# Ethernet.net
KiCad netlist of a schematic drawn in Altium Designer
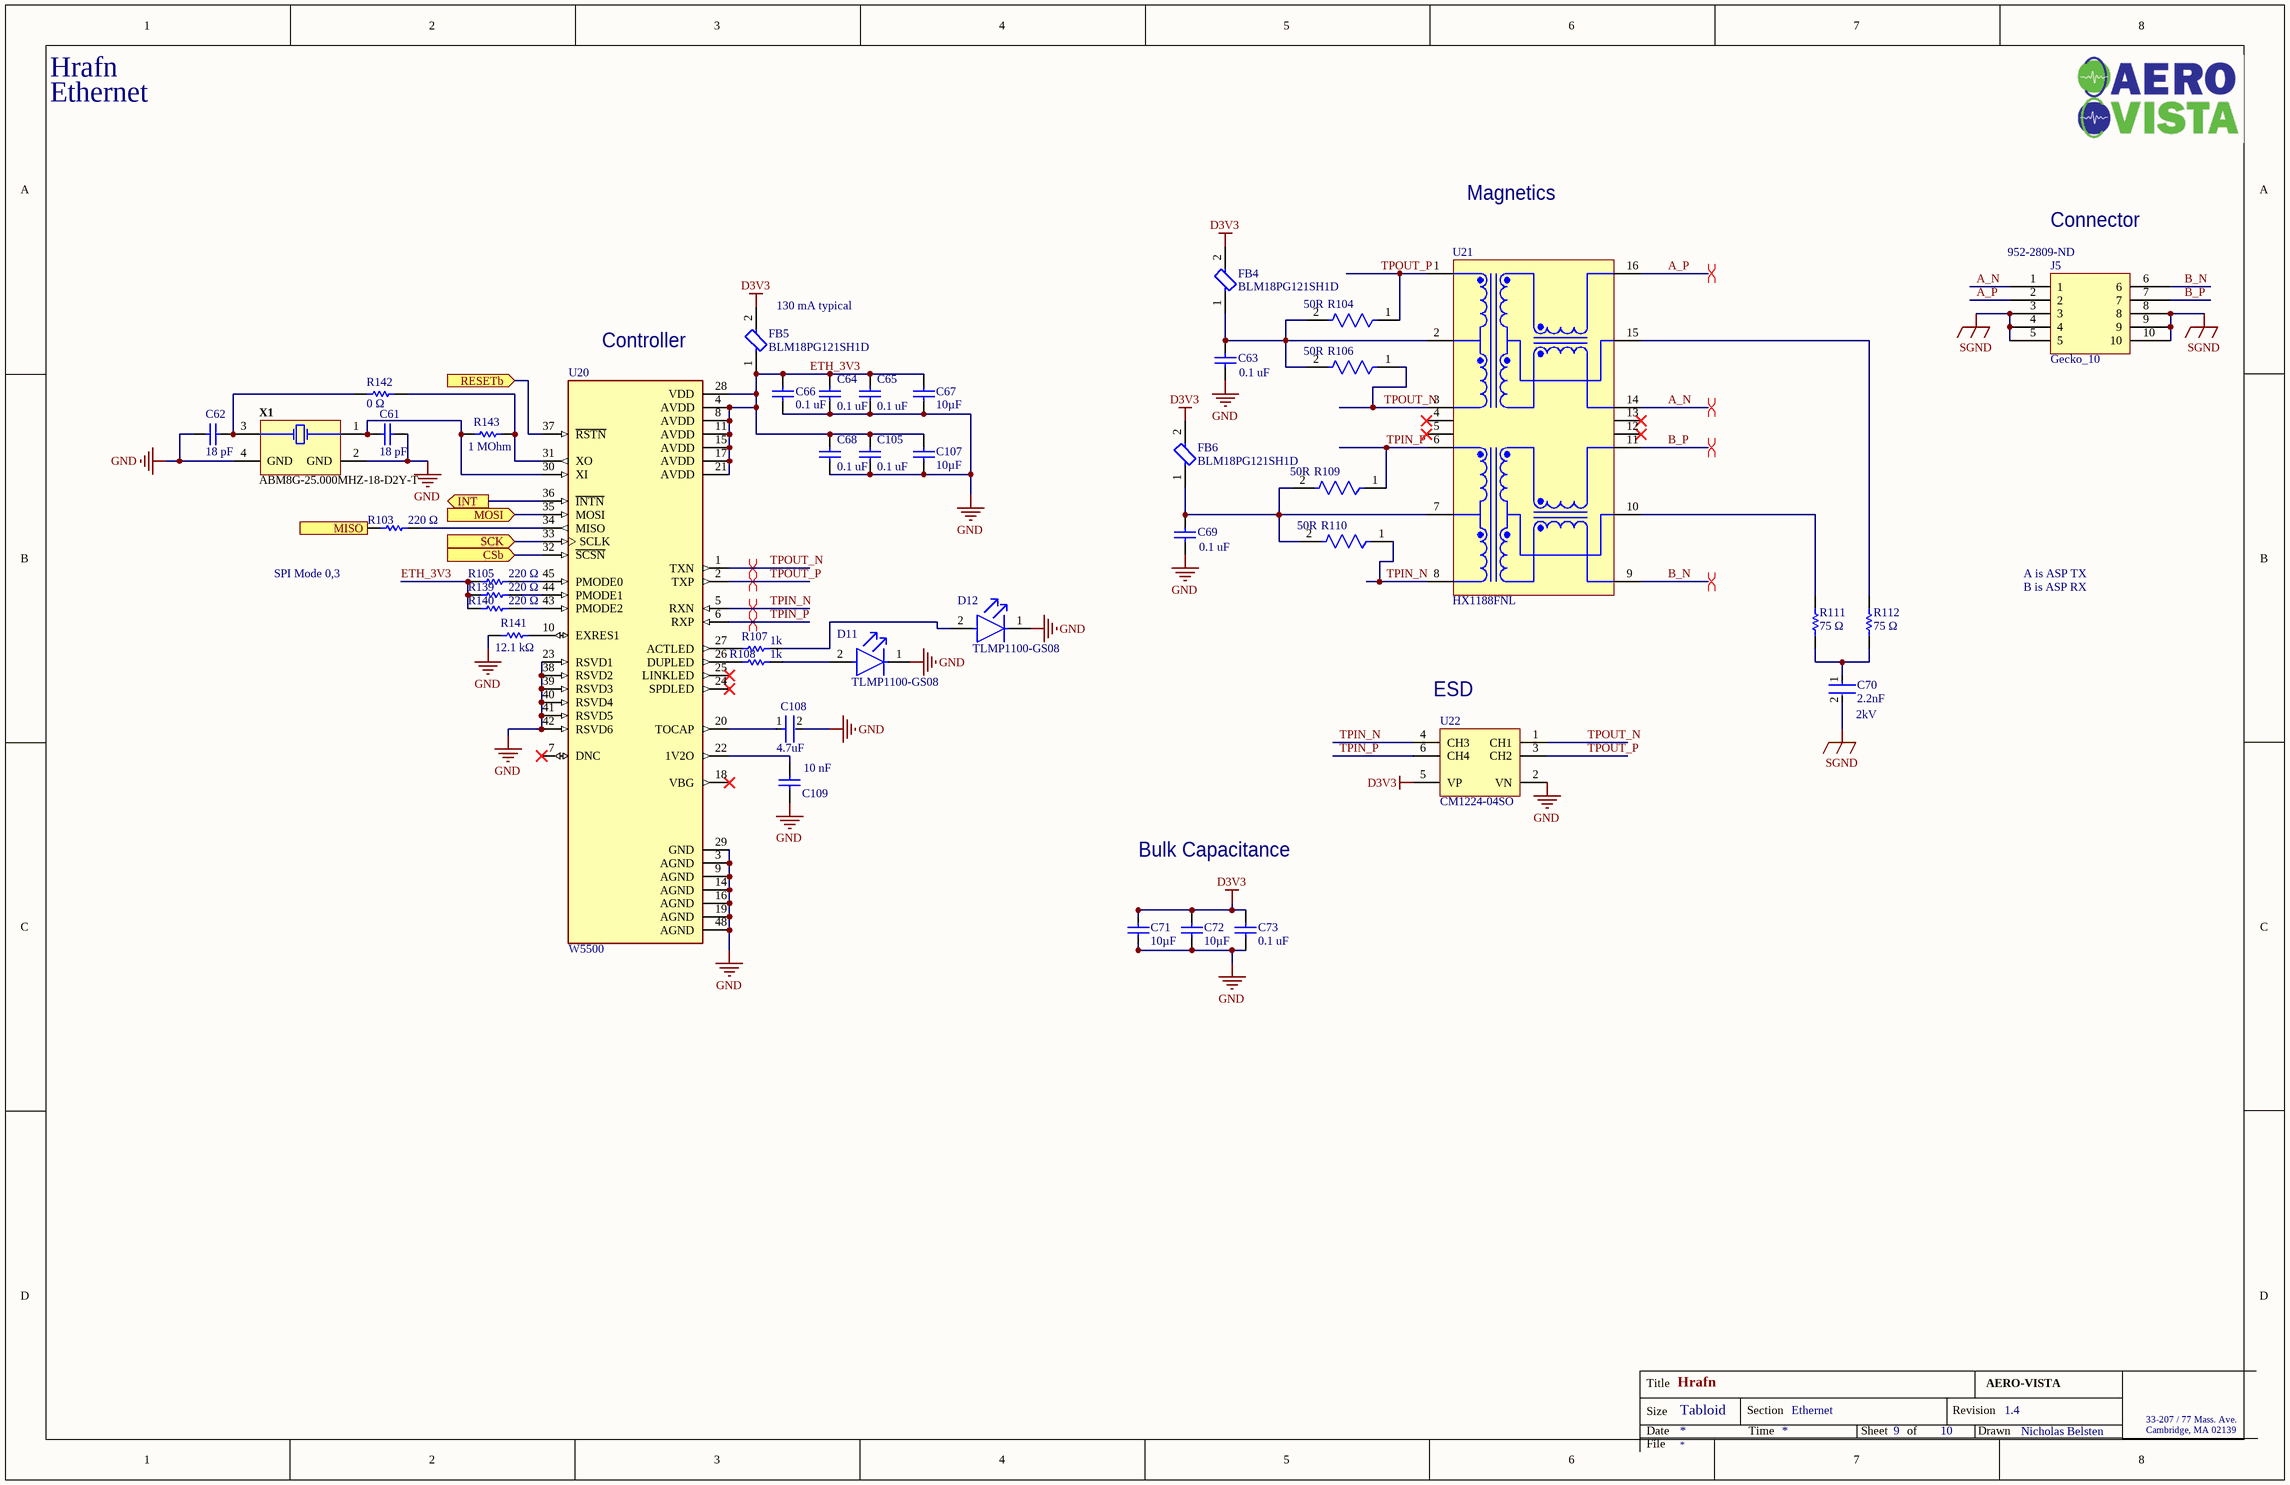
[diagram p0: Ethernet.SchDoc]

(export (version "E")
  (design (tool "Eeschema 10.0.6"))
  (components
    (comp (ref "C61")
      (value "GRM1555C1H180JA01D")
      (footprint "CAPC1005X55X25LL05T10")
      (fields (field (name "MANUFACTURER") "Murata") (field (name "CAPACITANCE") "18 pF"))
      (libsource (lib "Altium Content Vault") (part "CAP"))
    )
    (comp (ref "C62")
      (value "GRM1555C1H180JA01D")
      (footprint "CAPC1005X55X25LL05T10")
      (fields (field (name "MANUFACTURER") "Murata") (field (name "CAPACITANCE") "18 pF"))
      (libsource (lib "Altium Content Vault") (part "CAP"))
    )
    (comp (ref "C63")
      (value "0.1 uF")
      (footprint "CAPC0402(1005)60_L")
      (description "CAP 100nF 16V ±5% 0402 (1005 Metric) Thickness 0.6mm SMD")
      (fields (field (name "TOLERANCE") "Â±5%"))
      (libsource (lib "Altium Content Vault") (part "CAP"))
    )
    (comp (ref "C64")
      (value "0.1 uF")
      (footprint "CAPC0402(1005)60_L")
      (description "CAP 100nF 16V ±5% 0402 (1005 Metric) Thickness 0.6mm SMD")
      (fields (field (name "TOLERANCE") "Â±5%"))
      (libsource (lib "Altium Content Vault") (part "CAP"))
    )
    (comp (ref "C65")
      (value "0.1 uF")
      (footprint "CAPC0402(1005)60_L")
      (description "CAP 100nF 16V ±5% 0402 (1005 Metric) Thickness 0.6mm SMD")
      (fields (field (name "TOLERANCE") "Â±5%"))
      (libsource (lib "Altium Content Vault") (part "CAP"))
    )
    (comp (ref "C66")
      (value "0.1 uF")
      (footprint "CAPC0402(1005)60_L")
      (description "CAP 100nF 16V ±5% 0402 (1005 Metric) Thickness 0.6mm SMD")
      (fields (field (name "TOLERANCE") "Â±5%"))
      (libsource (lib "Altium Content Vault") (part "CAP"))
    )
    (comp (ref "C67")
      (value "EMK107BBJ106MA-T")
      (footprint "CAPC1608X100X35LL20T25")
      (description "Chip Capacitor, 10 uF, +/- 20%, 16 V, -55 to 85 degC, 0603 (1608 Metric), RoHS, Tape and Reel")
      (fields
        (field (name "CAPACITANCE") "10µF")
        (field (name "MANUFACTURER") "Taiyo Yuden")
        (field (name "TOLERANCE") "±20%")
      )
      (libsource (lib "Altium Content Vault") (part "CAP-NP-2"))
    )
    (comp (ref "C68")
      (value "0.1 uF")
      (footprint "CAPC0402(1005)60_L")
      (description "CAP 100nF 16V ±5% 0402 (1005 Metric) Thickness 0.6mm SMD")
      (fields (field (name "TOLERANCE") "Â±5%"))
      (libsource (lib "Altium Content Vault") (part "CAP"))
    )
    (comp (ref "C69")
      (value "0.1 uF")
      (footprint "CAPC0402(1005)60_L")
      (description "CAP 100nF 16V ±5% 0402 (1005 Metric) Thickness 0.6mm SMD")
      (fields (field (name "TOLERANCE") "Â±5%"))
      (libsource (lib "Altium Content Vault") (part "CAP"))
    )
    (comp (ref "C70")
      (value "2.2nF")
      (footprint "FP-CGA6P-MFG")
      (description "Cap Ceramic 2.2nF 2000V X7S 20% Pad SMD 1210 +125°C Automotive T/R")
      (fields (field (name "VOLTAGE RATING (DC)") "2kV") (field (name "TOLERANCE") "20%"))
      (libsource (lib "Altium Content Vault") (part "b4654b650e69147ec39a6b967a45e02"))
    )
    (comp (ref "C71")
      (value "EMK107BBJ106MA-T")
      (footprint "CAPC1608X100X35LL20T25")
      (description "Chip Capacitor, 10 uF, +/- 20%, 16 V, -55 to 85 degC, 0603 (1608 Metric), RoHS, Tape and Reel")
      (fields
        (field (name "CAPACITANCE") "10µF")
        (field (name "MANUFACTURER") "Taiyo Yuden")
        (field (name "TOLERANCE") "±20%")
      )
      (libsource (lib "Altium Content Vault") (part "CAP-NP-2"))
    )
    (comp (ref "C72")
      (value "EMK107BBJ106MA-T")
      (footprint "CAPC1608X100X35LL20T25")
      (description "Chip Capacitor, 10 uF, +/- 20%, 16 V, -55 to 85 degC, 0603 (1608 Metric), RoHS, Tape and Reel")
      (fields
        (field (name "CAPACITANCE") "10µF")
        (field (name "MANUFACTURER") "Taiyo Yuden")
        (field (name "TOLERANCE") "±20%")
      )
      (libsource (lib "Altium Content Vault") (part "CAP-NP-2"))
    )
    (comp (ref "C73")
      (value "0.1 uF")
      (footprint "CAPC0402(1005)60_L")
      (description "CAP 100nF 16V ±5% 0402 (1005 Metric) Thickness 0.6mm SMD")
      (fields (field (name "TOLERANCE") "Â±5%"))
      (libsource (lib "Altium Content Vault") (part "CAP"))
    )
    (comp (ref "C105")
      (value "0.1 uF")
      (footprint "CAPC0402(1005)60_L")
      (description "CAP 100nF 16V ±5% 0402 (1005 Metric) Thickness 0.6mm SMD")
      (fields (field (name "TOLERANCE") "Â±5%"))
      (libsource (lib "Altium Content Vault") (part "CAP"))
    )
    (comp (ref "C107")
      (value "EMK107BBJ106MA-T")
      (footprint "CAPC1608X100X35LL20T25")
      (description "Chip Capacitor, 10 uF, +/- 20%, 16 V, -55 to 85 degC, 0603 (1608 Metric), RoHS, Tape and Reel")
      (fields
        (field (name "CAPACITANCE") "10µF")
        (field (name "MANUFACTURER") "Taiyo Yuden")
        (field (name "TOLERANCE") "±20%")
      )
      (libsource (lib "Altium Content Vault") (part "CAP-NP-2"))
    )
    (comp (ref "C108")
      (value "GRM188R6YA475KE15D")
      (footprint "FP-GRM188-0_2-IPC_C")
      (description "Chip Multilayer Ceramic Capacitors for General Purpose, 0603, 4.7uF, X5R, 15%, 10%, 35V")
      (fields
        (field (name "CAPACITANCE") "4.7uF")
        (field (name "VOLTAGE") "35V")
        (field (name "TOLERANCE") "10%")
      )
      (libsource (lib "Altium Content Vault") (part "11868f565c42a9108669ba33697ecf6"))
    )
    (comp (ref "C109")
      (value "GRM155R71E103KA01D")
      (footprint "CAPC1005X55X25LL05T10")
      (fields (field (name "MANUFACTURER") "Murata") (field (name "CAPACITANCE") "10 nF"))
      (libsource (lib "Altium Content Vault") (part "CAP"))
    )
    (comp (ref "D11")
      (value "TLMP1100-GS08")
      (footprint "FP-6_541-5056_01-4-MFG")
      (description "LED GREEN 0603 SMD")
      (fields
        (field (name "MANUFACTURER") "Vishay")
        (field (name "OCTOPART") "https://octopart.com/tlmp1100-gs08-vishay-55433993")
      )
      (libsource (lib "Altium Content Vault") (part "8706943c75ba83719d021d2fdc84c58"))
    )
    (comp (ref "D12")
      (value "TLMP1100-GS08")
      (footprint "FP-6_541-5056_01-4-MFG")
      (description "LED GREEN 0603 SMD")
      (fields
        (field (name "MANUFACTURER") "Vishay")
        (field (name "OCTOPART") "https://octopart.com/tlmp1100-gs08-vishay-55433993")
      )
      (libsource (lib "Altium Content Vault") (part "8706943c75ba83719d021d2fdc84c58"))
    )
    (comp (ref "FB4")
      (value "BLM18PG121SH1D")
      (footprint "FP-BLM18-0_15-t0_8-IPC_C")
      (description "Chip Ferrite Bead, 0603, 120Ω @ 100MHz, 0.05Ω, 25%, 2A")
      (fields (field (name "TOLERANCE") "25%"))
      (libsource (lib "Altium Content Vault") (part "5f30dd21d616792df468990f7003faa"))
    )
    (comp (ref "FB5")
      (value "BLM18PG121SH1D")
      (footprint "FP-BLM18-0_15-t0_8-IPC_C")
      (description "Chip Ferrite Bead, 0603, 120Ω @ 100MHz, 0.05Ω, 25%, 2A")
      (fields (field (name "TOLERANCE") "25%"))
      (libsource (lib "Altium Content Vault") (part "5f30dd21d616792df468990f7003faa"))
    )
    (comp (ref "FB6")
      (value "BLM18PG121SH1D")
      (footprint "FP-BLM18-0_15-t0_8-IPC_C")
      (description "Chip Ferrite Bead, 0603, 120Ω @ 100MHz, 0.05Ω, 25%, 2A")
      (fields (field (name "TOLERANCE") "25%"))
      (libsource (lib "Altium Content Vault") (part "5f30dd21d616792df468990f7003faa"))
    )
    (comp (ref "J5")
      (value "Gecko_10")
      (footprint "GECK10-dup")
      (description "Headers & Wire Housings 1.25MM M VERT 3.0MM 2x5 POS")
      (fields (field (name "SUPPLIER PART NUMBER 1") "952-2809-ND"))
      (libsource (lib "Hrafn") (part "Gecko_10"))
    )
    (comp (ref "R103")
      (value "220 Ω")
      (footprint "RESC1005X40X25LL05T05")
      (fields (field (name "PART NUMBER") "CRCW040220K0FKED") (field (name "MANUFACTURER") "Vishay Dale"))
      (libsource (lib "Altium Content Vault") (part "RES"))
    )
    (comp (ref "R104")
      (value "CRCW060350R0FKEA")
      (footprint "FP-CRCW0603-e3-MFG")
      (description "RES Thick Film, 50Ω, 1%, 0.1W, 100ppm/°C, 0603")
      (fields (field (name "RESISTANCE") "50R") (field (name "TOLERANCE") "1%"))
      (libsource (lib "Altium Content Vault") (part "1029c3af85768c4190bb7ad29bc67b5"))
    )
    (comp (ref "R105")
      (value "220 Ω")
      (footprint "RESC1005X40X25LL05T05")
      (fields (field (name "PART NUMBER") "CRCW040220K0FKED") (field (name "MANUFACTURER") "Vishay Dale"))
      (libsource (lib "Altium Content Vault") (part "RES"))
    )
    (comp (ref "R106")
      (value "CRCW060350R0FKEA")
      (footprint "FP-CRCW0603-e3-MFG")
      (description "RES Thick Film, 50Ω, 1%, 0.1W, 100ppm/°C, 0603")
      (fields (field (name "RESISTANCE") "50R") (field (name "TOLERANCE") "1%"))
      (libsource (lib "Altium Content Vault") (part "1029c3af85768c4190bb7ad29bc67b5"))
    )
    (comp (ref "R107")
      (value "ERJ-2GEJ102X")
      (footprint "RESC1005X40X25LL05T05")
      (fields (field (name "MANUFACTURER") "Panasonic") (field (name "RESISTANCE") "1k"))
      (libsource (lib "Altium Content Vault") (part "RES"))
    )
    (comp (ref "R108")
      (value "ERJ-2GEJ102X")
      (footprint "RESC1005X40X25LL05T05")
      (fields (field (name "MANUFACTURER") "Panasonic") (field (name "RESISTANCE") "1k"))
      (libsource (lib "Altium Content Vault") (part "RES"))
    )
    (comp (ref "R109")
      (value "CRCW060350R0FKEA")
      (footprint "FP-CRCW0603-e3-MFG")
      (description "RES Thick Film, 50Ω, 1%, 0.1W, 100ppm/°C, 0603")
      (fields (field (name "RESISTANCE") "50R") (field (name "TOLERANCE") "1%"))
      (libsource (lib "Altium Content Vault") (part "1029c3af85768c4190bb7ad29bc67b5"))
    )
    (comp (ref "R110")
      (value "CRCW060350R0FKEA")
      (footprint "FP-CRCW0603-e3-MFG")
      (description "RES Thick Film, 50Ω, 1%, 0.1W, 100ppm/°C, 0603")
      (fields (field (name "RESISTANCE") "50R") (field (name "TOLERANCE") "1%"))
      (libsource (lib "Altium Content Vault") (part "1029c3af85768c4190bb7ad29bc67b5"))
    )
    (comp (ref "R111")
      (value "75 Ω")
      (footprint "RESC1005X40X25NL05T05")
      (fields (field (name "MANUFACTURER") "Panasonic") (field (name "PART NUMBER") "ERJ-2RKF75R0X"))
      (libsource (lib "Altium Content Vault") (part "RES"))
    )
    (comp (ref "R112")
      (value "75 Ω")
      (footprint "RESC1005X40X25NL05T05")
      (fields (field (name "MANUFACTURER") "Panasonic") (field (name "PART NUMBER") "ERJ-2RKF75R0X"))
      (libsource (lib "Altium Content Vault") (part "RES"))
    )
    (comp (ref "R139")
      (value "220 Ω")
      (footprint "RESC1005X40X25LL05T05")
      (fields (field (name "PART NUMBER") "CRCW040220K0FKED") (field (name "MANUFACTURER") "Vishay Dale"))
      (libsource (lib "Altium Content Vault") (part "RES"))
    )
    (comp (ref "R140")
      (value "220 Ω")
      (footprint "RESC1005X40X25LL05T05")
      (fields (field (name "PART NUMBER") "CRCW040220K0FKED") (field (name "MANUFACTURER") "Vishay Dale"))
      (libsource (lib "Altium Content Vault") (part "RES"))
    )
    (comp (ref "R141")
      (value "ERJ-2RKF1212X")
      (footprint "RESC1005X40X25LL05T05")
      (fields (field (name "MANUFACTURER") "Panasonic") (field (name "RESISTANCE") "12.1 kΩ"))
      (libsource (lib "Altium Content Vault") (part "RES"))
    )
    (comp (ref "R142")
      (value "ERJ2GE0R00X")
      (footprint "RESC1005X40X25LL05T05")
      (description "Chip Resistor, 0 Ohm, 0.1 W, -55 to 155 degC, 0402 (1005 Metric), RoHS, Tape and Reel")
      (fields
        (field (name "MANUFACTURER") "Panasonic")
        (field (name "RESISTANCE") "0 Ω")
        (field (name "TOLERANCE") "5%")
      )
      (libsource (lib "Altium Content Vault") (part "RES-2"))
    )
    (comp (ref "R143")
      (value "AC0402FR-071ML")
      (footprint "RESC1005X37X25LL05T10")
      (fields (field (name "MANUFACTURER") "Yageo") (field (name "RESISTANCE") "1 MOhm"))
      (libsource (lib "Altium Content Vault") (part "RES"))
    )
    (comp (ref "U20")
      (value "W5500")
      (footprint "TSQFP50P900X900X160-48L")
      (description "Socket Contact Silver 17-20 AWG Crimp Power")
      (fields (field (name "MF") "WIZnet"))
      (libsource (lib "W5500") (part "W5500"))
    )
    (comp (ref "U21")
      (value "HX1188FNL")
      (footprint "PULS-HX1188FNL-SMT-16_V")
      (description "Telecom Transformer 1:1/1:1, -40 to 85 degC, 16-Pin SMT, RoHS, Tube")
      (fields (field (name "MANUFACTURER") "Pulse Electronics"))
      (libsource (lib "Altium Content Vault") (part "PULS-HX1188FNL-16"))
    )
    (comp (ref "U22")
      (value "CM1224-04SO")
      (footprint "ONSC-SOT23-6-527AJ_V")
      (description "4-Channel Low Capacitance ESD Protection Array, 6-Pin SOT-23, Pb-Free, Tape and Reel")
      (fields (field (name "MANUFACTURER") "On Semiconductor"))
      (libsource (lib "Altium Content Vault") (part "ONSC-CM1224-SOT-23-6-527AJ"))
    )
    (comp (ref "X1")
      (value "ABM8G-25.000MHZ-18-D2Y-T")
      (footprint "ABRA-ABM8G_V")
      (fields (field (name "MANUFACTURER") "ABRACON") (field (name "TOLERANCE") "20PPM"))
      (libsource (lib "Altium Content Vault") (part "XTAL-1-3-4"))
    )
  )
  (nets
    (net (code "1") (name "/A_N") (class "Default")
      (node (ref "J5") (pin "1") (pinfunction "1_1") (pintype "passive"))
      (node (ref "U21") (pin "14") (pinfunction "TX-_14") (pintype "passive"))
    )
    (net (code "2") (name "/A_P") (class "Default")
      (node (ref "J5") (pin "2") (pinfunction "2_2") (pintype "passive"))
      (node (ref "U21") (pin "16") (pinfunction "TX+_16") (pintype "passive"))
    )
    (net (code "3") (name "/B_N") (class "Default")
      (node (ref "J5") (pin "6") (pinfunction "6_6") (pintype "passive"))
      (node (ref "U21") (pin "9") (pinfunction "RX-_9") (pintype "passive"))
    )
    (net (code "4") (name "/B_P") (class "Default")
      (node (ref "J5") (pin "7") (pinfunction "7_7") (pintype "passive"))
      (node (ref "U21") (pin "11") (pinfunction "RX+_11") (pintype "passive"))
    )
    (net (code "5") (name "/CSb") (class "Default")
      (node (ref "U20") (pin "32") (pinfunction "~{SCSN}_32") (pintype "input"))
    )
    (net (code "6") (name "/ETH_3V3") (class "Default")
      (node (ref "C105") (pin "2") (pinfunction "2_2") (pintype "passive"))
      (node (ref "C107") (pin "1") (pinfunction "1_1") (pintype "passive"))
      (node (ref "C64") (pin "2") (pinfunction "2_2") (pintype "passive"))
      (node (ref "C65") (pin "2") (pinfunction "2_2") (pintype "passive"))
      (node (ref "C66") (pin "1") (pinfunction "1_1") (pintype "passive"))
      (node (ref "C67") (pin "1") (pinfunction "1_1") (pintype "passive"))
      (node (ref "C68") (pin "2") (pinfunction "2_2") (pintype "passive"))
      (node (ref "FB5") (pin "1") (pinfunction "1_1") (pintype "passive"))
      (node (ref "R105") (pin "1") (pinfunction "1_1") (pintype "passive"))
      (node (ref "R139") (pin "1") (pinfunction "1_1") (pintype "passive"))
      (node (ref "R140") (pin "1") (pinfunction "1_1") (pintype "passive"))
      (node (ref "U20") (pin "11") (pinfunction "AVDD_11") (pintype "power_in"))
      (node (ref "U20") (pin "15") (pinfunction "AVDD_15") (pintype "power_in"))
      (node (ref "U20") (pin "17") (pinfunction "AVDD_17") (pintype "power_in"))
      (node (ref "U20") (pin "21") (pinfunction "AVDD_21") (pintype "power_in"))
      (node (ref "U20") (pin "28") (pinfunction "VDD_28") (pintype "power_in"))
      (node (ref "U20") (pin "4") (pinfunction "AVDD_4") (pintype "power_in"))
      (node (ref "U20") (pin "8") (pinfunction "AVDD_8") (pintype "power_in"))
    )
    (net (code "7") (name "/INT") (class "Default")
      (node (ref "U20") (pin "36") (pinfunction "~{INTN}_36") (pintype "input"))
    )
    (net (code "8") (name "/MISO") (class "Default")
      (node (ref "R103") (pin "1") (pinfunction "1_1") (pintype "passive"))
    )
    (net (code "9") (name "/MOSI") (class "Default")
      (node (ref "U20") (pin "35") (pinfunction "MOSI_35") (pintype "input"))
    )
    (net (code "10") (name "/RESETb") (class "Default")
      (node (ref "U20") (pin "37") (pinfunction "~{RSTN}_37") (pintype "input"))
    )
    (net (code "11") (name "/SCK") (class "Default")
      (node (ref "U20") (pin "33") (pinfunction "SCLK_33") (pintype "input"))
    )
    (net (code "12") (name "/TPIN_N") (class "Default")
      (node (ref "R110") (pin "1") (pinfunction "1_1") (pintype "passive"))
      (node (ref "U20") (pin "5") (pinfunction "RXN_5") (pintype "input"))
      (node (ref "U21") (pin "8") (pinfunction "RD-_8") (pintype "passive"))
      (node (ref "U22") (pin "4") (pinfunction "CH3_4") (pintype "passive"))
    )
    (net (code "13") (name "/TPIN_P") (class "Default")
      (node (ref "R109") (pin "1") (pinfunction "1_1") (pintype "passive"))
      (node (ref "U20") (pin "6") (pinfunction "RXP_6") (pintype "input"))
      (node (ref "U21") (pin "6") (pinfunction "RD+_6") (pintype "passive"))
      (node (ref "U22") (pin "6") (pinfunction "CH4_6") (pintype "passive"))
    )
    (net (code "14") (name "/TPOUT_N") (class "Default")
      (node (ref "R106") (pin "1") (pinfunction "1_1") (pintype "passive"))
      (node (ref "U20") (pin "1") (pinfunction "TXN_1") (pintype "output"))
      (node (ref "U21") (pin "3") (pinfunction "TD-_3") (pintype "passive"))
      (node (ref "U22") (pin "1") (pinfunction "CH1_1") (pintype "passive"))
    )
    (net (code "15") (name "/TPOUT_P") (class "Default")
      (node (ref "R104") (pin "1") (pinfunction "1_1") (pintype "passive"))
      (node (ref "U20") (pin "2") (pinfunction "TXP_2") (pintype "output"))
      (node (ref "U21") (pin "1") (pinfunction "TD+_1") (pintype "passive"))
      (node (ref "U22") (pin "3") (pinfunction "CH2_3") (pintype "passive"))
    )
    (net (code "16") (name "D3V3") (class "Default")
      (node (ref "C71") (pin "2") (pinfunction "2_2") (pintype "passive"))
      (node (ref "C72") (pin "2") (pinfunction "2_2") (pintype "passive"))
      (node (ref "C73") (pin "2") (pinfunction "2_2") (pintype "passive"))
      (node (ref "FB4") (pin "2") (pinfunction "2_2") (pintype "passive"))
      (node (ref "FB5") (pin "2") (pinfunction "2_2") (pintype "passive"))
      (node (ref "FB6") (pin "2") (pinfunction "2_2") (pintype "passive"))
      (node (ref "U22") (pin "5") (pinfunction "VP_5") (pintype "power_in"))
    )
    (net (code "17") (name "GND") (class "Default")
      (node (ref "C105") (pin "1") (pinfunction "1_1") (pintype "passive"))
      (node (ref "C107") (pin "2") (pinfunction "2_2") (pintype "passive"))
      (node (ref "C108") (pin "2") (pinfunction "2_2") (pintype "passive"))
      (node (ref "C109") (pin "1") (pinfunction "1_1") (pintype "passive"))
      (node (ref "C61") (pin "1") (pinfunction "1_1") (pintype "passive"))
      (node (ref "C62") (pin "2") (pinfunction "2_2") (pintype "passive"))
      (node (ref "C63") (pin "1") (pinfunction "1_1") (pintype "passive"))
      (node (ref "C64") (pin "1") (pinfunction "1_1") (pintype "passive"))
      (node (ref "C65") (pin "1") (pinfunction "1_1") (pintype "passive"))
      (node (ref "C66") (pin "2") (pinfunction "2_2") (pintype "passive"))
      (node (ref "C67") (pin "2") (pinfunction "2_2") (pintype "passive"))
      (node (ref "C68") (pin "1") (pinfunction "1_1") (pintype "passive"))
      (node (ref "C69") (pin "1") (pinfunction "1_1") (pintype "passive"))
      (node (ref "C71") (pin "1") (pinfunction "1_1") (pintype "passive"))
      (node (ref "C72") (pin "1") (pinfunction "1_1") (pintype "passive"))
      (node (ref "C73") (pin "1") (pinfunction "1_1") (pintype "passive"))
      (node (ref "D11") (pin "1") (pinfunction "C_1") (pintype "passive"))
      (node (ref "D12") (pin "1") (pinfunction "C_1") (pintype "passive"))
      (node (ref "R141") (pin "1") (pinfunction "1_1") (pintype "passive"))
      (node (ref "U20") (pin "14") (pinfunction "AGND_14") (pintype "power_in"))
      (node (ref "U20") (pin "16") (pinfunction "AGND_16") (pintype "power_in"))
      (node (ref "U20") (pin "19") (pinfunction "AGND_19") (pintype "power_in"))
      (node (ref "U20") (pin "23") (pinfunction "RSVD1_23") (pintype "input"))
      (node (ref "U20") (pin "29") (pinfunction "GND_29") (pintype "passive"))
      (node (ref "U20") (pin "3") (pinfunction "AGND_3") (pintype "power_in"))
      (node (ref "U20") (pin "38") (pinfunction "RSVD2_38") (pintype "input"))
      (node (ref "U20") (pin "39") (pinfunction "RSVD3_39") (pintype "input"))
      (node (ref "U20") (pin "40") (pinfunction "RSVD4_40") (pintype "input"))
      (node (ref "U20") (pin "41") (pinfunction "RSVD5_41") (pintype "input"))
      (node (ref "U20") (pin "42") (pinfunction "RSVD6_42") (pintype "input"))
      (node (ref "U20") (pin "48") (pinfunction "AGND_48") (pintype "power_in"))
      (node (ref "U20") (pin "9") (pinfunction "AGND_9") (pintype "power_in"))
      (node (ref "U22") (pin "2") (pinfunction "VN_2") (pintype "power_in"))
      (node (ref "X1") (pin "2") (pinfunction "GND_2") (pintype "power_in"))
      (node (ref "X1") (pin "4") (pinfunction "GND_4") (pintype "power_in"))
    )
    (net (code "18") (name "Net-(C70-Pad1)") (class "Default")
      (node (ref "C70") (pin "1") (pinfunction "1_1") (pintype "passive"))
      (node (ref "R111") (pin "1") (pinfunction "1_1") (pintype "passive"))
      (node (ref "R112") (pin "1") (pinfunction "1_1") (pintype "passive"))
    )
    (net (code "19") (name "Net-(D11-A)") (class "Default")
      (node (ref "D11") (pin "2") (pinfunction "A_2") (pintype "passive"))
      (node (ref "R108") (pin "2") (pinfunction "2_2") (pintype "passive"))
    )
    (net (code "20") (name "Net-(D12-A)") (class "Default")
      (node (ref "D12") (pin "2") (pinfunction "A_2") (pintype "passive"))
      (node (ref "R107") (pin "2") (pinfunction "2_2") (pintype "passive"))
    )
    (net (code "21") (name "Net-(R111-Pad2)") (class "Default")
      (node (ref "R111") (pin "2") (pinfunction "2_2") (pintype "passive"))
      (node (ref "U21") (pin "10") (pinfunction "CMT_10") (pintype "passive"))
    )
    (net (code "22") (name "Net-(R112-Pad2)") (class "Default")
      (node (ref "R112") (pin "2") (pinfunction "2_2") (pintype "passive"))
      (node (ref "U21") (pin "15") (pinfunction "CMT_15") (pintype "passive"))
    )
    (net (code "23") (name "Net-(U20-1V2O)") (class "Default")
      (node (ref "C109") (pin "2") (pinfunction "2_2") (pintype "passive"))
      (node (ref "U20") (pin "22") (pinfunction "1V2O_22") (pintype "output"))
    )
    (net (code "24") (name "Net-(U20-ACTLED)") (class "Default")
      (node (ref "R107") (pin "1") (pinfunction "1_1") (pintype "passive"))
      (node (ref "U20") (pin "27") (pinfunction "ACTLED_27") (pintype "output"))
    )
    (net (code "25") (name "Net-(U20-DUPLED)") (class "Default")
      (node (ref "R108") (pin "1") (pinfunction "1_1") (pintype "passive"))
      (node (ref "U20") (pin "26") (pinfunction "DUPLED_26") (pintype "output"))
    )
    (net (code "26") (name "Net-(U20-EXRES1)") (class "Default")
      (node (ref "R141") (pin "2") (pinfunction "2_2") (pintype "passive"))
      (node (ref "U20") (pin "10") (pinfunction "EXRES1_10") (pintype "bidirectional"))
    )
    (net (code "27") (name "Net-(U20-MISO)") (class "Default")
      (node (ref "R103") (pin "2") (pinfunction "2_2") (pintype "passive"))
      (node (ref "U20") (pin "34") (pinfunction "MISO_34") (pintype "output"))
    )
    (net (code "28") (name "Net-(U20-PMODE0)") (class "Default")
      (node (ref "R105") (pin "2") (pinfunction "2_2") (pintype "passive"))
      (node (ref "U20") (pin "45") (pinfunction "PMODE0_45") (pintype "input"))
    )
    (net (code "29") (name "Net-(U20-PMODE1)") (class "Default")
      (node (ref "R139") (pin "2") (pinfunction "2_2") (pintype "passive"))
      (node (ref "U20") (pin "44") (pinfunction "PMODE1_44") (pintype "input"))
    )
    (net (code "30") (name "Net-(U20-PMODE2)") (class "Default")
      (node (ref "R140") (pin "2") (pinfunction "2_2") (pintype "passive"))
      (node (ref "U20") (pin "43") (pinfunction "PMODE2_43") (pintype "input"))
    )
    (net (code "31") (name "Net-(U20-TOCAP)") (class "Default")
      (node (ref "C108") (pin "1") (pinfunction "1_1") (pintype "passive"))
      (node (ref "U20") (pin "20") (pinfunction "TOCAP_20") (pintype "output"))
    )
    (net (code "32") (name "Net-(U20-XI)") (class "Default")
      (node (ref "C61") (pin "2") (pinfunction "2_2") (pintype "passive"))
      (node (ref "R143") (pin "1") (pinfunction "1_1") (pintype "passive"))
      (node (ref "U20") (pin "30") (pinfunction "XI_30") (pintype "input"))
      (node (ref "X1") (pin "1") (pinfunction "X1_1") (pintype "passive"))
    )
    (net (code "33") (name "Net-(U20-XO)") (class "Default")
      (node (ref "R142") (pin "1") (pinfunction "1_1") (pintype "passive"))
      (node (ref "R143") (pin "2") (pinfunction "2_2") (pintype "passive"))
      (node (ref "U20") (pin "31") (pinfunction "XO_31") (pintype "output"))
    )
    (net (code "34") (name "Net-(U21-RCT)") (class "Default")
      (node (ref "C69") (pin "2") (pinfunction "2_2") (pintype "passive"))
      (node (ref "FB6") (pin "1") (pinfunction "1_1") (pintype "passive"))
      (node (ref "R109") (pin "2") (pinfunction "2_2") (pintype "passive"))
      (node (ref "R110") (pin "2") (pinfunction "2_2") (pintype "passive"))
      (node (ref "U21") (pin "7") (pinfunction "RCT_7") (pintype "passive"))
    )
    (net (code "35") (name "Net-(U21-TCT)") (class "Default")
      (node (ref "C63") (pin "2") (pinfunction "2_2") (pintype "passive"))
      (node (ref "FB4") (pin "1") (pinfunction "1_1") (pintype "passive"))
      (node (ref "R104") (pin "2") (pinfunction "2_2") (pintype "passive"))
      (node (ref "R106") (pin "2") (pinfunction "2_2") (pintype "passive"))
      (node (ref "U21") (pin "2") (pinfunction "TCT_2") (pintype "passive"))
    )
    (net (code "36") (name "Net-(X1-X2)") (class "Default")
      (node (ref "C62") (pin "1") (pinfunction "1_1") (pintype "passive"))
      (node (ref "R142") (pin "2") (pinfunction "2_2") (pintype "passive"))
      (node (ref "X1") (pin "3") (pinfunction "X2_3") (pintype "passive"))
    )
    (net (code "37") (name "SGND") (class "Default")
      (node (ref "C70") (pin "2") (pinfunction "2_2") (pintype "passive"))
      (node (ref "J5") (pin "10") (pinfunction "10_10") (pintype "passive"))
      (node (ref "J5") (pin "3") (pinfunction "3_3") (pintype "passive"))
      (node (ref "J5") (pin "4") (pinfunction "4_4") (pintype "passive"))
      (node (ref "J5") (pin "5") (pinfunction "5_5") (pintype "passive"))
      (node (ref "J5") (pin "8") (pinfunction "8_8") (pintype "passive"))
      (node (ref "J5") (pin "9") (pinfunction "9_9") (pintype "passive"))
    )
    (net (code "38") (name "unconnected-(U20-DNC-Pad7)") (class "Default")
      (node (ref "U20") (pin "7") (pinfunction "DNC_7") (pintype "bidirectional+no_connect"))
    )
    (net (code "39") (name "unconnected-(U20-LINKLED-Pad25)") (class "Default")
      (node (ref "U20") (pin "25") (pinfunction "LINKLED_25") (pintype "output+no_connect"))
    )
    (net (code "40") (name "unconnected-(U20-SPDLED-Pad24)") (class "Default")
      (node (ref "U20") (pin "24") (pinfunction "SPDLED_24") (pintype "output+no_connect"))
    )
    (net (code "41") (name "unconnected-(U20-VBG-Pad18)") (class "Default")
      (node (ref "U20") (pin "18") (pinfunction "VBG_18") (pintype "output+no_connect"))
    )
    (net (code "42") (name "unconnected-(U21-NC-Pad4)") (class "Default")
      (node (ref "U21") (pin "4") (pinfunction "NC_4") (pintype "passive+no_connect"))
    )
    (net (code "43") (name "unconnected-(U21-NC-Pad5)") (class "Default")
      (node (ref "U21") (pin "5") (pinfunction "NC_5") (pintype "passive+no_connect"))
    )
    (net (code "44") (name "unconnected-(U21-NC-Pad12)") (class "Default")
      (node (ref "U21") (pin "12") (pinfunction "NC_12") (pintype "passive+no_connect"))
    )
    (net (code "45") (name "unconnected-(U21-NC-Pad13)") (class "Default")
      (node (ref "U21") (pin "13") (pinfunction "NC_13") (pintype "passive+no_connect"))
    )
  )
)
